# STM32.net
KiCad netlist of a schematic drawn in Altium Designer
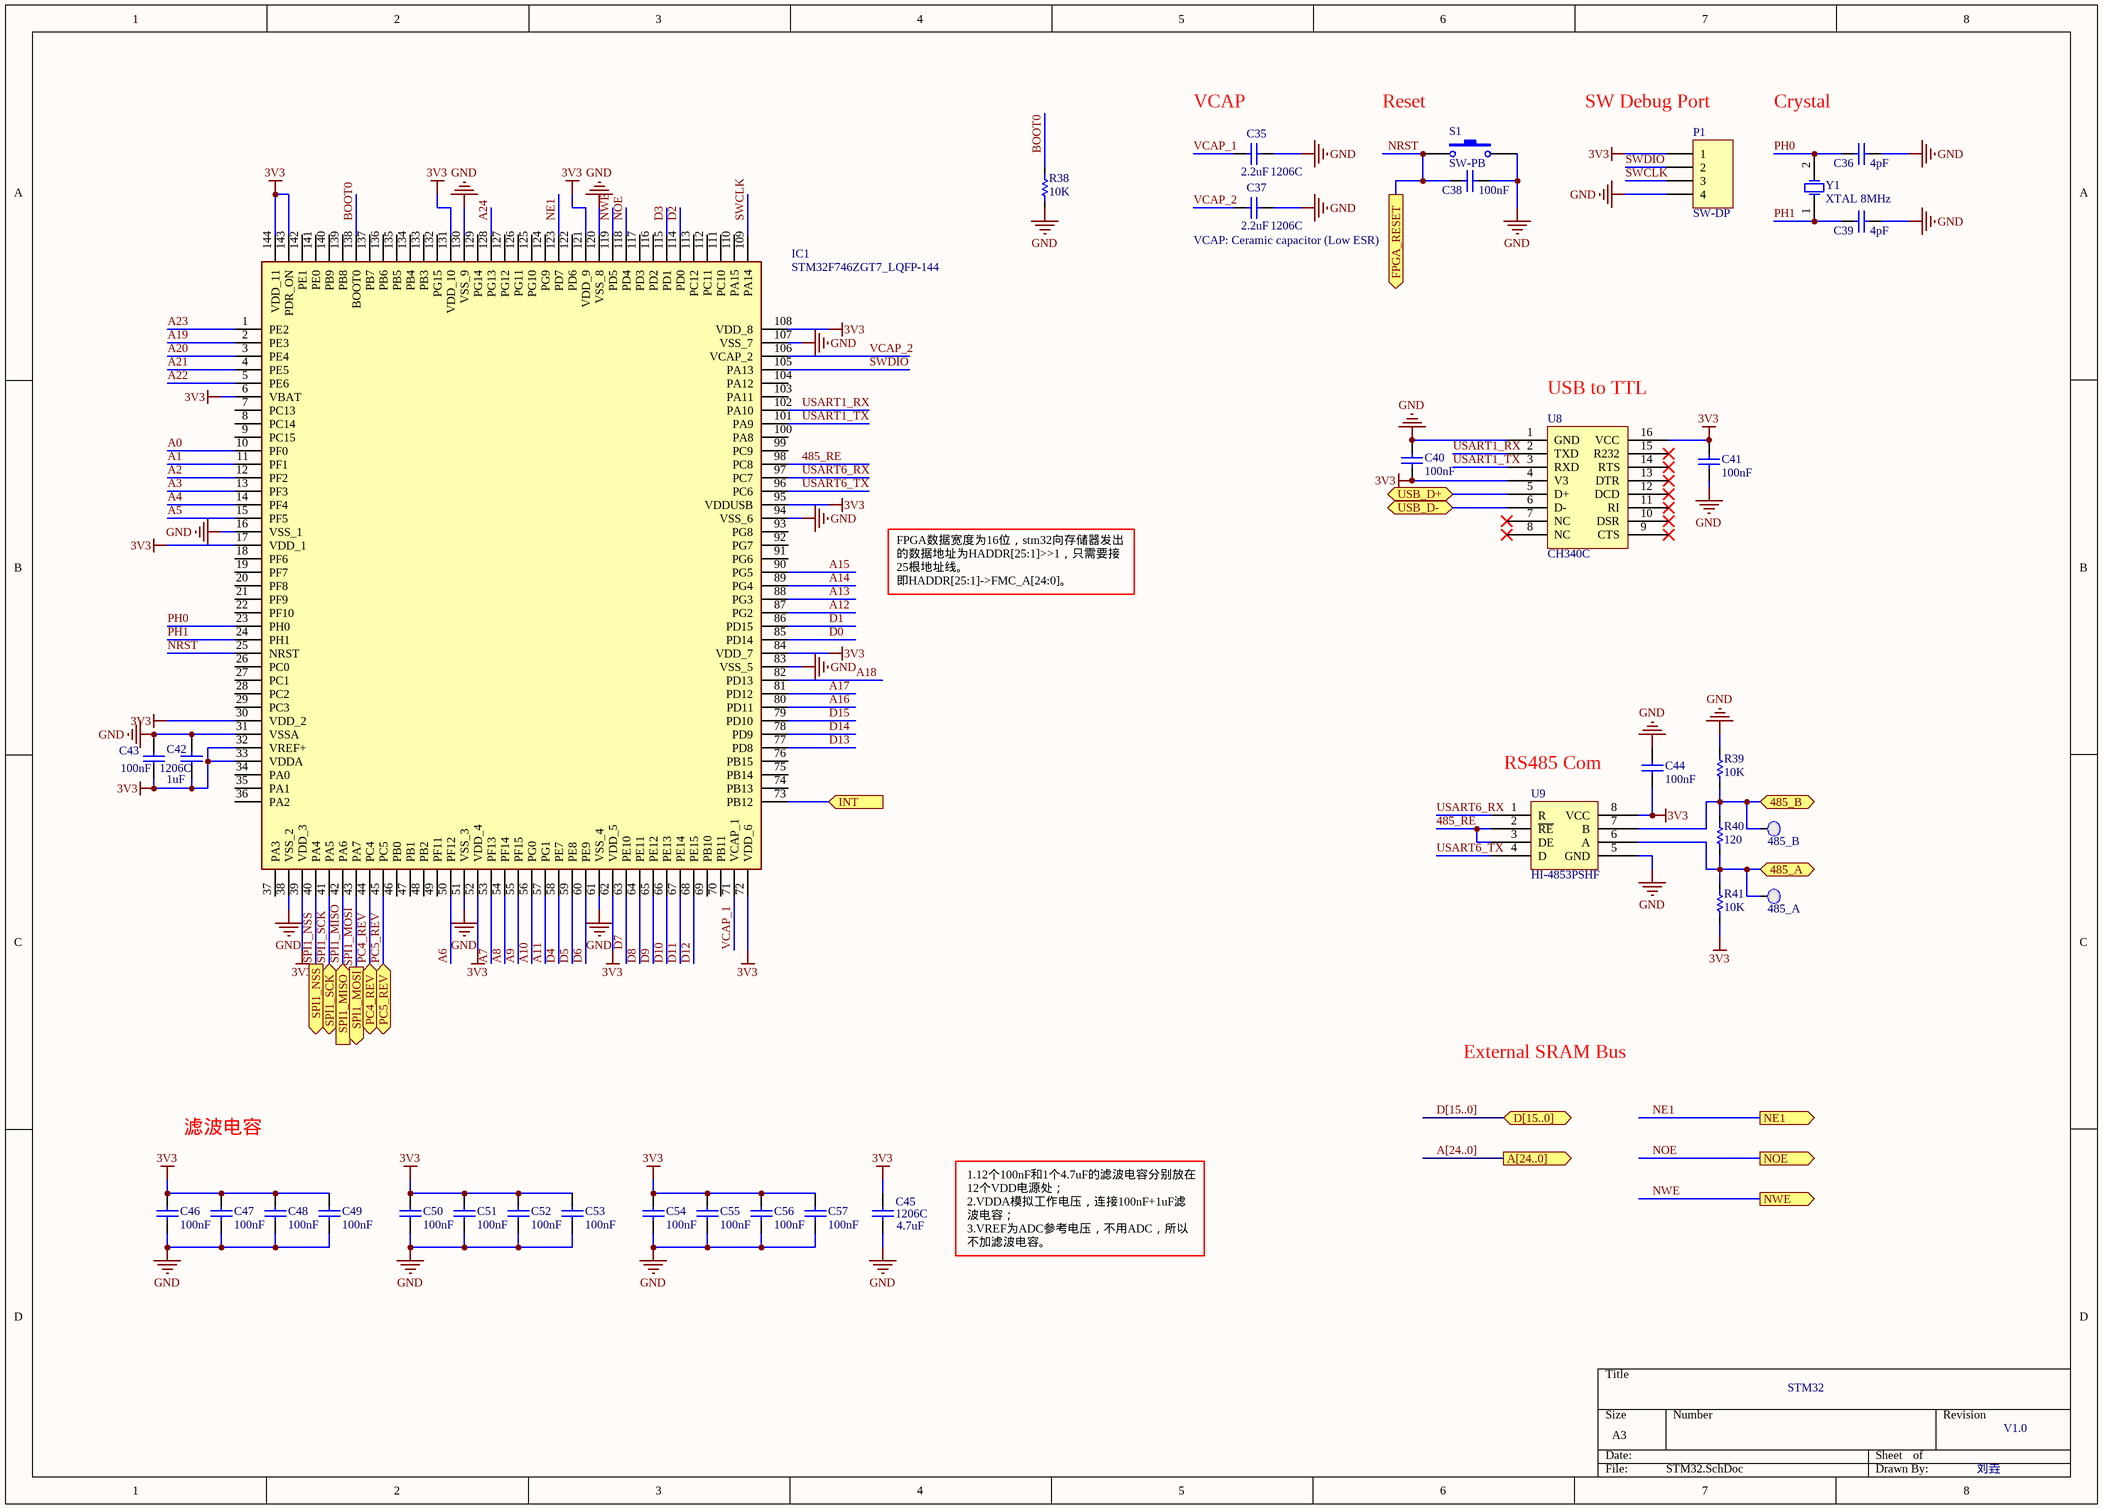
[diagram p0: STM32.SchDoc]

(export (version "E")
  (design (tool "Eeschema 10.0.6"))
  (components
    (comp (ref "485_A") (value "TP") (footprint "TPA") (libsource (lib "STM32") (part "TP")))
    (comp (ref "485_B") (value "TP") (footprint "TPA") (libsource (lib "STM32") (part "TP")))
    (comp (ref "C35")
      (value "2.2uF")
      (footprint "1206C")
      (description "Capacitor")
      (fields (field (name "PACKAGEREFERENCE") "1206C") (field (name "PUBLISHER") "Altium Limited"))
      (libsource (lib "STM32") (part "Cap"))
    )
    (comp (ref "C36")
      (value "4pF")
      (footprint "0805C")
      (description "Capacitor")
      (fields (field (name "PUBLISHER") "Altium Limited"))
      (libsource (lib "STM32") (part "Cap"))
    )
    (comp (ref "C37")
      (value "2.2uF")
      (footprint "1206C")
      (description "Capacitor")
      (fields (field (name "PACKAGEREFERENCE") "1206C") (field (name "PUBLISHER") "Altium Limited"))
      (libsource (lib "STM32") (part "Cap"))
    )
    (comp (ref "C38")
      (value "100nF")
      (footprint "0805C")
      (description "Capacitor")
      (fields (field (name "PUBLISHER") "Altium Limited"))
      (libsource (lib "STM32") (part "Cap"))
    )
    (comp (ref "C39")
      (value "4pF")
      (footprint "0805C")
      (description "Capacitor")
      (fields (field (name "PUBLISHER") "Altium Limited"))
      (libsource (lib "STM32") (part "Cap"))
    )
    (comp (ref "C40")
      (value "100nF")
      (footprint "0805C")
      (description "Capacitor")
      (fields (field (name "PUBLISHER") "Altium Limited"))
      (libsource (lib "STM32") (part "Cap"))
    )
    (comp (ref "C41")
      (value "100nF")
      (footprint "0805C")
      (description "Capacitor")
      (fields (field (name "PUBLISHER") "Altium Limited"))
      (libsource (lib "STM32") (part "Cap"))
    )
    (comp (ref "C42")
      (value "1uF")
      (footprint "1206C")
      (description "Capacitor")
      (fields (field (name "PACKAGEREFERENCE") "1206C") (field (name "PUBLISHER") "Altium Limited"))
      (libsource (lib "STM32") (part "Cap"))
    )
    (comp (ref "C43")
      (value "100nF")
      (footprint "0805C")
      (description "Capacitor")
      (fields (field (name "PUBLISHER") "Altium Limited"))
      (libsource (lib "STM32") (part "Cap"))
    )
    (comp (ref "C44")
      (value "100nF")
      (footprint "0805C")
      (description "Capacitor")
      (fields (field (name "PUBLISHER") "Altium Limited"))
      (libsource (lib "STM32") (part "Cap"))
    )
    (comp (ref "C45")
      (value "4.7uF")
      (footprint "1206C")
      (description "Capacitor")
      (fields (field (name "PACKAGEREFERENCE") "1206C") (field (name "PUBLISHER") "Altium Limited"))
      (libsource (lib "STM32") (part "Cap"))
    )
    (comp (ref "C46")
      (value "100nF")
      (footprint "0805C")
      (description "Capacitor")
      (fields (field (name "PUBLISHER") "Altium Limited"))
      (libsource (lib "STM32") (part "Cap"))
    )
    (comp (ref "C47")
      (value "100nF")
      (footprint "0805C")
      (description "Capacitor")
      (fields (field (name "PUBLISHER") "Altium Limited"))
      (libsource (lib "STM32") (part "Cap"))
    )
    (comp (ref "C48")
      (value "100nF")
      (footprint "0805C")
      (description "Capacitor")
      (fields (field (name "PUBLISHER") "Altium Limited"))
      (libsource (lib "STM32") (part "Cap"))
    )
    (comp (ref "C49")
      (value "100nF")
      (footprint "0805C")
      (description "Capacitor")
      (fields (field (name "PUBLISHER") "Altium Limited"))
      (libsource (lib "STM32") (part "Cap"))
    )
    (comp (ref "C50")
      (value "100nF")
      (footprint "0805C")
      (description "Capacitor")
      (fields (field (name "PUBLISHER") "Altium Limited"))
      (libsource (lib "STM32") (part "Cap"))
    )
    (comp (ref "C51")
      (value "100nF")
      (footprint "0805C")
      (description "Capacitor")
      (fields (field (name "PUBLISHER") "Altium Limited"))
      (libsource (lib "STM32") (part "Cap"))
    )
    (comp (ref "C52")
      (value "100nF")
      (footprint "0805C")
      (description "Capacitor")
      (fields (field (name "PUBLISHER") "Altium Limited"))
      (libsource (lib "STM32") (part "Cap"))
    )
    (comp (ref "C53")
      (value "100nF")
      (footprint "0805C")
      (description "Capacitor")
      (fields (field (name "PUBLISHER") "Altium Limited"))
      (libsource (lib "STM32") (part "Cap"))
    )
    (comp (ref "C54")
      (value "100nF")
      (footprint "0805C")
      (description "Capacitor")
      (fields (field (name "PUBLISHER") "Altium Limited"))
      (libsource (lib "STM32") (part "Cap"))
    )
    (comp (ref "C55")
      (value "100nF")
      (footprint "0805C")
      (description "Capacitor")
      (fields (field (name "PUBLISHER") "Altium Limited"))
      (libsource (lib "STM32") (part "Cap"))
    )
    (comp (ref "C56")
      (value "100nF")
      (footprint "0805C")
      (description "Capacitor")
      (fields (field (name "PUBLISHER") "Altium Limited"))
      (libsource (lib "STM32") (part "Cap"))
    )
    (comp (ref "C57")
      (value "100nF")
      (footprint "0805C")
      (description "Capacitor")
      (fields (field (name "PUBLISHER") "Altium Limited"))
      (libsource (lib "STM32") (part "Cap"))
    )
    (comp (ref "IC1")
      (value "STM32F746ZGT7_LQFP-144")
      (footprint "STM32:QFP50P2200X2200X160-144N")
      (description "Integrated Circuit")
      (fields
        (field (name "MANUFACTURER_PART_NUMBER") "STM32F746ZGT7")
        (field (name "MOUSER PART NUMBER") "511-STM32F746ZGT7")
      )
      (libsource (lib "*") (part "STM32F746ZGT7"))
    )
    (comp (ref "P1")
      (value "SW-DP")
      (footprint "MHDR1X4")
      (description "Header, 4-Pin")
      (fields (field (name "PUBLISHER") "Altium Limited"))
      (libsource (lib "Miscellaneous Connectors") (part "MHDR1X4"))
    )
    (comp (ref "R38")
      (value "10K")
      (footprint "0805R")
      (description "Resistor")
      (fields (field (name "PUBLISHER") "Altium Limited"))
      (libsource (lib "STM32") (part "Res1"))
    )
    (comp (ref "R39")
      (value "10K")
      (footprint "0805R")
      (description "Resistor")
      (fields (field (name "PUBLISHER") "Altium Limited"))
      (libsource (lib "STM32") (part "Res1"))
    )
    (comp (ref "R40")
      (value "120")
      (footprint "0805R")
      (description "Resistor")
      (fields (field (name "PUBLISHER") "Altium Limited"))
      (libsource (lib "STM32") (part "Res1"))
    )
    (comp (ref "R41")
      (value "10K")
      (footprint "0805R")
      (description "Resistor")
      (fields (field (name "PUBLISHER") "Altium Limited"))
      (libsource (lib "STM32") (part "Res1"))
    )
    (comp (ref "S1")
      (value "SW-PB")
      (footprint "SW-SMD_L6.0-W3.5-LS8.0")
      (description "Switch")
      (fields (field (name "PUBLISHER") "Altium Limited"))
      (libsource (lib "Miscellaneous Devices") (part "SW-PB"))
    )
    (comp (ref "U8") (value "CH340C") (footprint "CH340C") (libsource (lib "STM32") (part "CH340C")))
    (comp (ref "U9")
      (value "HI-4853PSHF")
      (footprint "SOIC-8N")
      (libsource (lib "STM32") (part "HI-4853PSHF"))
    )
    (comp (ref "Y1")
      (value "XTAL 8MHz")
      (footprint "NX3225GD8MHZSTDCRA3")
      (description "Crystal Oscillator")
      (fields (field (name "PUBLISHER") "Altium Limited"))
      (libsource (lib "STM32") (part "XTAL"))
    )
  )
  (nets
    (net (code "1") (name "/485_A") (class "Default")
      (node (ref "485_A") (pin "1") (pinfunction "TP_1") (pintype "passive"))
      (node (ref "R40") (pin "1") (pinfunction "1_1") (pintype "passive"))
      (node (ref "R41") (pin "2") (pinfunction "2_2") (pintype "passive"))
      (node (ref "U9") (pin "6") (pinfunction "A_6") (pintype "passive"))
    )
    (net (code "2") (name "/485_B") (class "Default")
      (node (ref "485_B") (pin "1") (pinfunction "TP_1") (pintype "passive"))
      (node (ref "R39") (pin "1") (pinfunction "1_1") (pintype "passive"))
      (node (ref "R40") (pin "2") (pinfunction "2_2") (pintype "passive"))
      (node (ref "U9") (pin "7") (pinfunction "B_7") (pintype "passive"))
    )
    (net (code "3") (name "/485_RE") (class "Default")
      (node (ref "IC1") (pin "98") (pinfunction "PC8_98") (pintype "passive"))
      (node (ref "U9") (pin "2") (pinfunction "~{RE}_2") (pintype "passive"))
      (node (ref "U9") (pin "3") (pinfunction "DE_3") (pintype "passive"))
    )
    (net (code "4") (name "/A0") (class "Default")
      (node (ref "IC1") (pin "10") (pinfunction "PF0_10") (pintype "passive"))
    )
    (net (code "5") (name "/A1") (class "Default")
      (node (ref "IC1") (pin "11") (pinfunction "PF1_11") (pintype "passive"))
    )
    (net (code "6") (name "/A2") (class "Default")
      (node (ref "IC1") (pin "12") (pinfunction "PF2_12") (pintype "passive"))
    )
    (net (code "7") (name "/A3") (class "Default")
      (node (ref "IC1") (pin "13") (pinfunction "PF3_13") (pintype "passive"))
    )
    (net (code "8") (name "/A4") (class "Default")
      (node (ref "IC1") (pin "14") (pinfunction "PF4_14") (pintype "passive"))
    )
    (net (code "9") (name "/A5") (class "Default")
      (node (ref "IC1") (pin "15") (pinfunction "PF5_15") (pintype "passive"))
    )
    (net (code "10") (name "/A6") (class "Default")
      (node (ref "IC1") (pin "50") (pinfunction "PF12_50") (pintype "passive"))
    )
    (net (code "11") (name "/A7") (class "Default")
      (node (ref "IC1") (pin "53") (pinfunction "PF13_53") (pintype "passive"))
    )
    (net (code "12") (name "/A8") (class "Default")
      (node (ref "IC1") (pin "54") (pinfunction "PF14_54") (pintype "passive"))
    )
    (net (code "13") (name "/A9") (class "Default")
      (node (ref "IC1") (pin "55") (pinfunction "PF15_55") (pintype "passive"))
    )
    (net (code "14") (name "/A10") (class "Default")
      (node (ref "IC1") (pin "56") (pinfunction "PG0_56") (pintype "passive"))
    )
    (net (code "15") (name "/A11") (class "Default")
      (node (ref "IC1") (pin "57") (pinfunction "PG1_57") (pintype "passive"))
    )
    (net (code "16") (name "/A12") (class "Default")
      (node (ref "IC1") (pin "87") (pinfunction "PG2_87") (pintype "passive"))
    )
    (net (code "17") (name "/A13") (class "Default")
      (node (ref "IC1") (pin "88") (pinfunction "PG3_88") (pintype "passive"))
    )
    (net (code "18") (name "/A14") (class "Default")
      (node (ref "IC1") (pin "89") (pinfunction "PG4_89") (pintype "passive"))
    )
    (net (code "19") (name "/A15") (class "Default")
      (node (ref "IC1") (pin "90") (pinfunction "PG5_90") (pintype "passive"))
    )
    (net (code "20") (name "/A16") (class "Default")
      (node (ref "IC1") (pin "80") (pinfunction "PD11_80") (pintype "passive"))
    )
    (net (code "21") (name "/A17") (class "Default")
      (node (ref "IC1") (pin "81") (pinfunction "PD12_81") (pintype "passive"))
    )
    (net (code "22") (name "/A18") (class "Default")
      (node (ref "IC1") (pin "82") (pinfunction "PD13_82") (pintype "passive"))
    )
    (net (code "23") (name "/A19") (class "Default")
      (node (ref "IC1") (pin "2") (pinfunction "PE3_2") (pintype "passive"))
    )
    (net (code "24") (name "/A20") (class "Default")
      (node (ref "IC1") (pin "3") (pinfunction "PE4_3") (pintype "passive"))
    )
    (net (code "25") (name "/A21") (class "Default")
      (node (ref "IC1") (pin "4") (pinfunction "PE5_4") (pintype "passive"))
    )
    (net (code "26") (name "/A22") (class "Default")
      (node (ref "IC1") (pin "5") (pinfunction "PE6_5") (pintype "passive"))
    )
    (net (code "27") (name "/A23") (class "Default")
      (node (ref "IC1") (pin "1") (pinfunction "PE2_1") (pintype "passive"))
    )
    (net (code "28") (name "/A24") (class "Default")
      (node (ref "IC1") (pin "128") (pinfunction "PG13_128") (pintype "passive"))
    )
    (net (code "30") (name "/BOOT0") (class "Default")
      (node (ref "IC1") (pin "138") (pinfunction "BOOT0_138") (pintype "passive"))
      (node (ref "R38") (pin "1") (pinfunction "1_1") (pintype "passive"))
    )
    (net (code "31") (name "/D0") (class "Default")
      (node (ref "IC1") (pin "85") (pinfunction "PD14_85") (pintype "passive"))
    )
    (net (code "32") (name "/D1") (class "Default")
      (node (ref "IC1") (pin "86") (pinfunction "PD15_86") (pintype "passive"))
    )
    (net (code "33") (name "/D2") (class "Default")
      (node (ref "IC1") (pin "114") (pinfunction "PD0_114") (pintype "passive"))
    )
    (net (code "34") (name "/D3") (class "Default")
      (node (ref "IC1") (pin "115") (pinfunction "PD1_115") (pintype "passive"))
    )
    (net (code "35") (name "/D4") (class "Default")
      (node (ref "IC1") (pin "58") (pinfunction "PE7_58") (pintype "passive"))
    )
    (net (code "36") (name "/D5") (class "Default")
      (node (ref "IC1") (pin "59") (pinfunction "PE8_59") (pintype "passive"))
    )
    (net (code "37") (name "/D6") (class "Default")
      (node (ref "IC1") (pin "60") (pinfunction "PE9_60") (pintype "passive"))
    )
    (net (code "38") (name "/D7") (class "Default")
      (node (ref "IC1") (pin "63") (pinfunction "PE10_63") (pintype "passive"))
    )
    (net (code "39") (name "/D8") (class "Default")
      (node (ref "IC1") (pin "64") (pinfunction "PE11_64") (pintype "passive"))
    )
    (net (code "40") (name "/D9") (class "Default")
      (node (ref "IC1") (pin "65") (pinfunction "PE12_65") (pintype "passive"))
    )
    (net (code "41") (name "/D10") (class "Default")
      (node (ref "IC1") (pin "66") (pinfunction "PE13_66") (pintype "passive"))
    )
    (net (code "42") (name "/D11") (class "Default")
      (node (ref "IC1") (pin "67") (pinfunction "PE14_67") (pintype "passive"))
    )
    (net (code "43") (name "/D12") (class "Default")
      (node (ref "IC1") (pin "68") (pinfunction "PE15_68") (pintype "passive"))
    )
    (net (code "44") (name "/D13") (class "Default")
      (node (ref "IC1") (pin "77") (pinfunction "PD8_77") (pintype "passive"))
    )
    (net (code "45") (name "/D14") (class "Default")
      (node (ref "IC1") (pin "78") (pinfunction "PD9_78") (pintype "passive"))
    )
    (net (code "46") (name "/D15") (class "Default")
      (node (ref "IC1") (pin "79") (pinfunction "PD10_79") (pintype "passive"))
    )
    (net (code "48") (name "/INT") (class "Default")
      (node (ref "IC1") (pin "73") (pinfunction "PB12_73") (pintype "passive"))
    )
    (net (code "49") (name "/NE1") (class "Default")
      (node (ref "IC1") (pin "123") (pinfunction "PD7_123") (pintype "passive"))
    )
    (net (code "50") (name "/NOE") (class "Default")
      (node (ref "IC1") (pin "118") (pinfunction "PD4_118") (pintype "passive"))
    )
    (net (code "51") (name "/NRST") (class "Default")
      (node (ref "C38") (pin "1") (pinfunction "1_1") (pintype "passive"))
      (node (ref "IC1") (pin "25") (pinfunction "NRST_25") (pintype "passive"))
      (node (ref "S1") (pin "1") (pinfunction "1_1") (pintype "passive"))
    )
    (net (code "52") (name "/NWE") (class "Default")
      (node (ref "IC1") (pin "119") (pinfunction "PD5_119") (pintype "passive"))
    )
    (net (code "53") (name "/PC4_REV") (class "Default")
      (node (ref "IC1") (pin "44") (pinfunction "PC4_44") (pintype "passive"))
    )
    (net (code "54") (name "/PC5_REV") (class "Default")
      (node (ref "IC1") (pin "45") (pinfunction "PC5_45") (pintype "passive"))
    )
    (net (code "55") (name "/PH0") (class "Default")
      (node (ref "C36") (pin "1") (pinfunction "1_1") (pintype "passive"))
      (node (ref "IC1") (pin "23") (pinfunction "PH0_23") (pintype "passive"))
      (node (ref "Y1") (pin "2") (pinfunction "OSC2_2") (pintype "passive"))
    )
    (net (code "56") (name "/PH1") (class "Default")
      (node (ref "C39") (pin "1") (pinfunction "1_1") (pintype "passive"))
      (node (ref "IC1") (pin "24") (pinfunction "PH1_24") (pintype "passive"))
      (node (ref "Y1") (pin "1") (pinfunction "OSC1_1") (pintype "passive"))
    )
    (net (code "57") (name "/SPI1_MISO") (class "Default")
      (node (ref "IC1") (pin "42") (pinfunction "PA6_42") (pintype "passive"))
    )
    (net (code "58") (name "/SPI1_MOSI") (class "Default")
      (node (ref "IC1") (pin "43") (pinfunction "PA7_43") (pintype "passive"))
    )
    (net (code "59") (name "/SPI1_NSS") (class "Default")
      (node (ref "IC1") (pin "40") (pinfunction "PA4_40") (pintype "passive"))
    )
    (net (code "60") (name "/SPI1_SCK") (class "Default")
      (node (ref "IC1") (pin "41") (pinfunction "PA5_41") (pintype "passive"))
    )
    (net (code "61") (name "/SWCLK") (class "Default")
      (node (ref "IC1") (pin "109") (pinfunction "PA14_109") (pintype "passive"))
      (node (ref "P1") (pin "3") (pinfunction "3_3") (pintype "passive"))
    )
    (net (code "62") (name "/SWDIO") (class "Default")
      (node (ref "IC1") (pin "105") (pinfunction "PA13_105") (pintype "passive"))
      (node (ref "P1") (pin "2") (pinfunction "2_2") (pintype "passive"))
    )
    (net (code "63") (name "/USART1_RX") (class "Default")
      (node (ref "IC1") (pin "102") (pinfunction "PA10_102") (pintype "passive"))
      (node (ref "U8") (pin "2") (pinfunction "TXD_2") (pintype "passive"))
    )
    (net (code "64") (name "/USART1_TX") (class "Default")
      (node (ref "IC1") (pin "101") (pinfunction "PA9_101") (pintype "passive"))
      (node (ref "U8") (pin "3") (pinfunction "RXD_3") (pintype "passive"))
    )
    (net (code "65") (name "/USART6_RX") (class "Default")
      (node (ref "IC1") (pin "97") (pinfunction "PC7_97") (pintype "passive"))
      (node (ref "U9") (pin "1") (pinfunction "R_1") (pintype "passive"))
    )
    (net (code "66") (name "/USART6_TX") (class "Default")
      (node (ref "IC1") (pin "96") (pinfunction "PC6_96") (pintype "passive"))
      (node (ref "U9") (pin "4") (pinfunction "D_4") (pintype "passive"))
    )
    (net (code "67") (name "/USB_D+") (class "Default")
      (node (ref "U8") (pin "5") (pinfunction "D+_5") (pintype "passive"))
    )
    (net (code "68") (name "/USB_D-") (class "Default")
      (node (ref "U8") (pin "6") (pinfunction "D-_6") (pintype "passive"))
    )
    (net (code "69") (name "/VCAP_1") (class "Default")
      (node (ref "C35") (pin "2") (pinfunction "2_2") (pintype "passive"))
      (node (ref "IC1") (pin "71") (pinfunction "VCAP_1_71") (pintype "passive"))
    )
    (net (code "70") (name "/VCAP_2") (class "Default")
      (node (ref "C37") (pin "2") (pinfunction "2_2") (pintype "passive"))
      (node (ref "IC1") (pin "106") (pinfunction "VCAP_2_106") (pintype "passive"))
    )
    (net (code "71") (name "3V3") (class "Default")
      (node (ref "C40") (pin "1") (pinfunction "1_1") (pintype "passive"))
      (node (ref "C41") (pin "2") (pinfunction "2_2") (pintype "passive"))
      (node (ref "C42") (pin "1") (pinfunction "1_1") (pintype "passive"))
      (node (ref "C43") (pin "1") (pinfunction "1_1") (pintype "passive"))
      (node (ref "C44") (pin "1") (pinfunction "1_1") (pintype "passive"))
      (node (ref "C45") (pin "2") (pinfunction "2_2") (pintype "passive"))
      (node (ref "C46") (pin "2") (pinfunction "2_2") (pintype "passive"))
      (node (ref "C47") (pin "2") (pinfunction "2_2") (pintype "passive"))
      (node (ref "C48") (pin "2") (pinfunction "2_2") (pintype "passive"))
      (node (ref "C49") (pin "2") (pinfunction "2_2") (pintype "passive"))
      (node (ref "C50") (pin "2") (pinfunction "2_2") (pintype "passive"))
      (node (ref "C51") (pin "2") (pinfunction "2_2") (pintype "passive"))
      (node (ref "C52") (pin "2") (pinfunction "2_2") (pintype "passive"))
      (node (ref "C53") (pin "2") (pinfunction "2_2") (pintype "passive"))
      (node (ref "C54") (pin "2") (pinfunction "2_2") (pintype "passive"))
      (node (ref "C55") (pin "2") (pinfunction "2_2") (pintype "passive"))
      (node (ref "C56") (pin "2") (pinfunction "2_2") (pintype "passive"))
      (node (ref "C57") (pin "2") (pinfunction "2_2") (pintype "passive"))
      (node (ref "IC1") (pin "108") (pinfunction "VDD_8_108") (pintype "passive"))
      (node (ref "IC1") (pin "121") (pinfunction "VDD_9_121") (pintype "passive"))
      (node (ref "IC1") (pin "131") (pinfunction "VDD_10_131") (pintype "passive"))
      (node (ref "IC1") (pin "143") (pinfunction "PDR_ON_143") (pintype "passive"))
      (node (ref "IC1") (pin "144") (pinfunction "VDD_11_144") (pintype "passive"))
      (node (ref "IC1") (pin "17") (pinfunction "VDD_1_17") (pintype "passive"))
      (node (ref "IC1") (pin "30") (pinfunction "VDD_2_30") (pintype "passive"))
      (node (ref "IC1") (pin "32") (pinfunction "VREF+_32") (pintype "passive"))
      (node (ref "IC1") (pin "33") (pinfunction "VDDA_33") (pintype "passive"))
      (node (ref "IC1") (pin "39") (pinfunction "VDD_3_39") (pintype "passive"))
      (node (ref "IC1") (pin "52") (pinfunction "VDD_4_52") (pintype "passive"))
      (node (ref "IC1") (pin "6") (pinfunction "VBAT_6") (pintype "passive"))
      (node (ref "IC1") (pin "62") (pinfunction "VDD_5_62") (pintype "passive"))
      (node (ref "IC1") (pin "72") (pinfunction "VDD_6_72") (pintype "passive"))
      (node (ref "IC1") (pin "84") (pinfunction "VDD_7_84") (pintype "passive"))
      (node (ref "IC1") (pin "95") (pinfunction "VDDUSB_95") (pintype "passive"))
      (node (ref "P1") (pin "1") (pinfunction "1_1") (pintype "passive"))
      (node (ref "R41") (pin "1") (pinfunction "1_1") (pintype "passive"))
      (node (ref "U8") (pin "16") (pinfunction "VCC_16") (pintype "passive"))
      (node (ref "U8") (pin "4") (pinfunction "V3_4") (pintype "power_in"))
      (node (ref "U9") (pin "8") (pinfunction "VCC_8") (pintype "passive"))
    )
    (net (code "72") (name "GND") (class "Default")
      (node (ref "C35") (pin "1") (pinfunction "1_1") (pintype "passive"))
      (node (ref "C36") (pin "2") (pinfunction "2_2") (pintype "passive"))
      (node (ref "C37") (pin "1") (pinfunction "1_1") (pintype "passive"))
      (node (ref "C38") (pin "2") (pinfunction "2_2") (pintype "passive"))
      (node (ref "C39") (pin "2") (pinfunction "2_2") (pintype "passive"))
      (node (ref "C40") (pin "2") (pinfunction "2_2") (pintype "passive"))
      (node (ref "C41") (pin "1") (pinfunction "1_1") (pintype "passive"))
      (node (ref "C42") (pin "2") (pinfunction "2_2") (pintype "passive"))
      (node (ref "C43") (pin "2") (pinfunction "2_2") (pintype "passive"))
      (node (ref "C44") (pin "2") (pinfunction "2_2") (pintype "passive"))
      (node (ref "C45") (pin "1") (pinfunction "1_1") (pintype "passive"))
      (node (ref "C46") (pin "1") (pinfunction "1_1") (pintype "passive"))
      (node (ref "C47") (pin "1") (pinfunction "1_1") (pintype "passive"))
      (node (ref "C48") (pin "1") (pinfunction "1_1") (pintype "passive"))
      (node (ref "C49") (pin "1") (pinfunction "1_1") (pintype "passive"))
      (node (ref "C50") (pin "1") (pinfunction "1_1") (pintype "passive"))
      (node (ref "C51") (pin "1") (pinfunction "1_1") (pintype "passive"))
      (node (ref "C52") (pin "1") (pinfunction "1_1") (pintype "passive"))
      (node (ref "C53") (pin "1") (pinfunction "1_1") (pintype "passive"))
      (node (ref "C54") (pin "1") (pinfunction "1_1") (pintype "passive"))
      (node (ref "C55") (pin "1") (pinfunction "1_1") (pintype "passive"))
      (node (ref "C56") (pin "1") (pinfunction "1_1") (pintype "passive"))
      (node (ref "C57") (pin "1") (pinfunction "1_1") (pintype "passive"))
      (node (ref "IC1") (pin "107") (pinfunction "VSS_7_107") (pintype "passive"))
      (node (ref "IC1") (pin "120") (pinfunction "VSS_8_120") (pintype "passive"))
      (node (ref "IC1") (pin "130") (pinfunction "VSS_9_130") (pintype "passive"))
      (node (ref "IC1") (pin "16") (pinfunction "VSS_1_16") (pintype "passive"))
      (node (ref "IC1") (pin "31") (pinfunction "VSSA_31") (pintype "passive"))
      (node (ref "IC1") (pin "38") (pinfunction "VSS_2_38") (pintype "passive"))
      (node (ref "IC1") (pin "51") (pinfunction "VSS_3_51") (pintype "passive"))
      (node (ref "IC1") (pin "61") (pinfunction "VSS_4_61") (pintype "passive"))
      (node (ref "IC1") (pin "83") (pinfunction "VSS_5_83") (pintype "passive"))
      (node (ref "IC1") (pin "94") (pinfunction "VSS_6_94") (pintype "passive"))
      (node (ref "P1") (pin "4") (pinfunction "4_4") (pintype "passive"))
      (node (ref "R38") (pin "2") (pinfunction "2_2") (pintype "passive"))
      (node (ref "R39") (pin "2") (pinfunction "2_2") (pintype "passive"))
      (node (ref "S1") (pin "2") (pinfunction "2_2") (pintype "passive"))
      (node (ref "U8") (pin "1") (pinfunction "GND_1") (pintype "passive"))
      (node (ref "U9") (pin "5") (pinfunction "GND_5") (pintype "passive"))
    )
    (net (code "73") (name "unconnected-(IC1-PA0-Pad34)") (class "Default")
      (node (ref "IC1") (pin "34") (pinfunction "PA0_34") (pintype "passive"))
    )
    (net (code "74") (name "unconnected-(IC1-PA1-Pad35)") (class "Default")
      (node (ref "IC1") (pin "35") (pinfunction "PA1_35") (pintype "passive"))
    )
    (net (code "75") (name "unconnected-(IC1-PA2-Pad36)") (class "Default")
      (node (ref "IC1") (pin "36") (pinfunction "PA2_36") (pintype "passive"))
    )
    (net (code "76") (name "unconnected-(IC1-PA3-Pad37)") (class "Default")
      (node (ref "IC1") (pin "37") (pinfunction "PA3_37") (pintype "passive"))
    )
    (net (code "77") (name "unconnected-(IC1-PA8-Pad100)") (class "Default")
      (node (ref "IC1") (pin "100") (pinfunction "PA8_100") (pintype "passive"))
    )
    (net (code "78") (name "unconnected-(IC1-PA11-Pad103)") (class "Default")
      (node (ref "IC1") (pin "103") (pinfunction "PA11_103") (pintype "passive"))
    )
    (net (code "79") (name "unconnected-(IC1-PA12-Pad104)") (class "Default")
      (node (ref "IC1") (pin "104") (pinfunction "PA12_104") (pintype "passive"))
    )
    (net (code "80") (name "unconnected-(IC1-PA15-Pad110)") (class "Default")
      (node (ref "IC1") (pin "110") (pinfunction "PA15_110") (pintype "passive"))
    )
    (net (code "81") (name "unconnected-(IC1-PB0-Pad46)") (class "Default")
      (node (ref "IC1") (pin "46") (pinfunction "PB0_46") (pintype "passive"))
    )
    (net (code "82") (name "unconnected-(IC1-PB1-Pad47)") (class "Default")
      (node (ref "IC1") (pin "47") (pinfunction "PB1_47") (pintype "passive"))
    )
    (net (code "83") (name "unconnected-(IC1-PB2-Pad48)") (class "Default")
      (node (ref "IC1") (pin "48") (pinfunction "PB2_48") (pintype "passive"))
    )
    (net (code "84") (name "unconnected-(IC1-PB3-Pad133)") (class "Default")
      (node (ref "IC1") (pin "133") (pinfunction "PB3_133") (pintype "passive"))
    )
    (net (code "85") (name "unconnected-(IC1-PB4-Pad134)") (class "Default")
      (node (ref "IC1") (pin "134") (pinfunction "PB4_134") (pintype "passive"))
    )
    (net (code "86") (name "unconnected-(IC1-PB5-Pad135)") (class "Default")
      (node (ref "IC1") (pin "135") (pinfunction "PB5_135") (pintype "passive"))
    )
    (net (code "87") (name "unconnected-(IC1-PB6-Pad136)") (class "Default")
      (node (ref "IC1") (pin "136") (pinfunction "PB6_136") (pintype "passive"))
    )
    (net (code "88") (name "unconnected-(IC1-PB7-Pad137)") (class "Default")
      (node (ref "IC1") (pin "137") (pinfunction "PB7_137") (pintype "passive"))
    )
    (net (code "89") (name "unconnected-(IC1-PB8-Pad139)") (class "Default")
      (node (ref "IC1") (pin "139") (pinfunction "PB8_139") (pintype "passive"))
    )
    (net (code "90") (name "unconnected-(IC1-PB9-Pad140)") (class "Default")
      (node (ref "IC1") (pin "140") (pinfunction "PB9_140") (pintype "passive"))
    )
    (net (code "91") (name "unconnected-(IC1-PB10-Pad69)") (class "Default")
      (node (ref "IC1") (pin "69") (pinfunction "PB10_69") (pintype "passive"))
    )
    (net (code "92") (name "unconnected-(IC1-PB11-Pad70)") (class "Default")
      (node (ref "IC1") (pin "70") (pinfunction "PB11_70") (pintype "passive"))
    )
    (net (code "93") (name "unconnected-(IC1-PB13-Pad74)") (class "Default")
      (node (ref "IC1") (pin "74") (pinfunction "PB13_74") (pintype "passive"))
    )
    (net (code "94") (name "unconnected-(IC1-PB14-Pad75)") (class "Default")
      (node (ref "IC1") (pin "75") (pinfunction "PB14_75") (pintype "passive"))
    )
    (net (code "95") (name "unconnected-(IC1-PB15-Pad76)") (class "Default")
      (node (ref "IC1") (pin "76") (pinfunction "PB15_76") (pintype "passive"))
    )
    (net (code "96") (name "unconnected-(IC1-PC0-Pad26)") (class "Default")
      (node (ref "IC1") (pin "26") (pinfunction "PC0_26") (pintype "passive"))
    )
    (net (code "97") (name "unconnected-(IC1-PC1-Pad27)") (class "Default")
      (node (ref "IC1") (pin "27") (pinfunction "PC1_27") (pintype "passive"))
    )
    (net (code "98") (name "unconnected-(IC1-PC2-Pad28)") (class "Default")
      (node (ref "IC1") (pin "28") (pinfunction "PC2_28") (pintype "passive"))
    )
    (net (code "99") (name "unconnected-(IC1-PC3-Pad29)") (class "Default")
      (node (ref "IC1") (pin "29") (pinfunction "PC3_29") (pintype "passive"))
    )
    (net (code "100") (name "unconnected-(IC1-PC9-Pad99)") (class "Default")
      (node (ref "IC1") (pin "99") (pinfunction "PC9_99") (pintype "passive"))
    )
    (net (code "101") (name "unconnected-(IC1-PC10-Pad111)") (class "Default")
      (node (ref "IC1") (pin "111") (pinfunction "PC10_111") (pintype "passive"))
    )
    (net (code "102") (name "unconnected-(IC1-PC11-Pad112)") (class "Default")
      (node (ref "IC1") (pin "112") (pinfunction "PC11_112") (pintype "passive"))
    )
    (net (code "103") (name "unconnected-(IC1-PC12-Pad113)") (class "Default")
      (node (ref "IC1") (pin "113") (pinfunction "PC12_113") (pintype "passive"))
    )
    (net (code "104") (name "unconnected-(IC1-PC13-Pad7)") (class "Default")
      (node (ref "IC1") (pin "7") (pinfunction "PC13_7") (pintype "passive"))
    )
    (net (code "105") (name "unconnected-(IC1-PC14-Pad8)") (class "Default")
      (node (ref "IC1") (pin "8") (pinfunction "PC14_8") (pintype "passive"))
    )
    (net (code "106") (name "unconnected-(IC1-PC15-Pad9)") (class "Default")
      (node (ref "IC1") (pin "9") (pinfunction "PC15_9") (pintype "passive"))
    )
    (net (code "107") (name "unconnected-(IC1-PD2-Pad116)") (class "Default")
      (node (ref "IC1") (pin "116") (pinfunction "PD2_116") (pintype "passive"))
    )
    (net (code "108") (name "unconnected-(IC1-PD3-Pad117)") (class "Default")
      (node (ref "IC1") (pin "117") (pinfunction "PD3_117") (pintype "passive"))
    )
    (net (code "109") (name "unconnected-(IC1-PD6-Pad122)") (class "Default")
      (node (ref "IC1") (pin "122") (pinfunction "PD6_122") (pintype "passive"))
    )
    (net (code "110") (name "unconnected-(IC1-PE0-Pad141)") (class "Default")
      (node (ref "IC1") (pin "141") (pinfunction "PE0_141") (pintype "passive"))
    )
    (net (code "111") (name "unconnected-(IC1-PE1-Pad142)") (class "Default")
      (node (ref "IC1") (pin "142") (pinfunction "PE1_142") (pintype "passive"))
    )
    (net (code "112") (name "unconnected-(IC1-PF6-Pad18)") (class "Default")
      (node (ref "IC1") (pin "18") (pinfunction "PF6_18") (pintype "passive"))
    )
    (net (code "113") (name "unconnected-(IC1-PF7-Pad19)") (class "Default")
      (node (ref "IC1") (pin "19") (pinfunction "PF7_19") (pintype "passive"))
    )
    (net (code "114") (name "unconnected-(IC1-PF8-Pad20)") (class "Default")
      (node (ref "IC1") (pin "20") (pinfunction "PF8_20") (pintype "passive"))
    )
    (net (code "115") (name "unconnected-(IC1-PF9-Pad21)") (class "Default")
      (node (ref "IC1") (pin "21") (pinfunction "PF9_21") (pintype "passive"))
    )
    (net (code "116") (name "unconnected-(IC1-PF10-Pad22)") (class "Default")
      (node (ref "IC1") (pin "22") (pinfunction "PF10_22") (pintype "passive"))
    )
    (net (code "117") (name "unconnected-(IC1-PF11-Pad49)") (class "Default")
      (node (ref "IC1") (pin "49") (pinfunction "PF11_49") (pintype "passive"))
    )
    (net (code "118") (name "unconnected-(IC1-PG6-Pad91)") (class "Default")
      (node (ref "IC1") (pin "91") (pinfunction "PG6_91") (pintype "passive"))
    )
    (net (code "119") (name "unconnected-(IC1-PG7-Pad92)") (class "Default")
      (node (ref "IC1") (pin "92") (pinfunction "PG7_92") (pintype "passive"))
    )
    (net (code "120") (name "unconnected-(IC1-PG8-Pad93)") (class "Default")
      (node (ref "IC1") (pin "93") (pinfunction "PG8_93") (pintype "passive"))
    )
    (net (code "121") (name "unconnected-(IC1-PG9-Pad124)") (class "Default")
      (node (ref "IC1") (pin "124") (pinfunction "PG9_124") (pintype "passive"))
    )
    (net (code "122") (name "unconnected-(IC1-PG10-Pad125)") (class "Default")
      (node (ref "IC1") (pin "125") (pinfunction "PG10_125") (pintype "passive"))
    )
    (net (code "123") (name "unconnected-(IC1-PG11-Pad126)") (class "Default")
      (node (ref "IC1") (pin "126") (pinfunction "PG11_126") (pintype "passive"))
    )
    (net (code "124") (name "unconnected-(IC1-PG12-Pad127)") (class "Default")
      (node (ref "IC1") (pin "127") (pinfunction "PG12_127") (pintype "passive"))
    )
    (net (code "125") (name "unconnected-(IC1-PG14-Pad129)") (class "Default")
      (node (ref "IC1") (pin "129") (pinfunction "PG14_129") (pintype "passive"))
    )
    (net (code "126") (name "unconnected-(IC1-PG15-Pad132)") (class "Default")
      (node (ref "IC1") (pin "132") (pinfunction "PG15_132") (pintype "passive"))
    )
    (net (code "127") (name "unconnected-(U8-CTS-Pad9)") (class "Default")
      (node (ref "U8") (pin "9") (pinfunction "CTS_9") (pintype "passive+no_connect"))
    )
    (net (code "128") (name "unconnected-(U8-DCD-Pad12)") (class "Default")
      (node (ref "U8") (pin "12") (pinfunction "DCD_12") (pintype "passive+no_connect"))
    )
    (net (code "129") (name "unconnected-(U8-DSR-Pad10)") (class "Default")
      (node (ref "U8") (pin "10") (pinfunction "DSR_10") (pintype "passive+no_connect"))
    )
    (net (code "130") (name "unconnected-(U8-DTR-Pad13)") (class "Default")
      (node (ref "U8") (pin "13") (pinfunction "DTR_13") (pintype "passive+no_connect"))
    )
    (net (code "131") (name "unconnected-(U8-NC-Pad7)") (class "Default")
      (node (ref "U8") (pin "7") (pinfunction "NC_7") (pintype "passive+no_connect"))
    )
    (net (code "132") (name "unconnected-(U8-NC-Pad8)") (class "Default")
      (node (ref "U8") (pin "8") (pinfunction "NC_8") (pintype "passive+no_connect"))
    )
    (net (code "133") (name "unconnected-(U8-R232-Pad15)") (class "Default")
      (node (ref "U8") (pin "15") (pinfunction "R232_15") (pintype "passive+no_connect"))
    )
    (net (code "134") (name "unconnected-(U8-RI-Pad11)") (class "Default")
      (node (ref "U8") (pin "11") (pinfunction "RI_11") (pintype "passive+no_connect"))
    )
    (net (code "135") (name "unconnected-(U8-RTS-Pad14)") (class "Default")
      (node (ref "U8") (pin "14") (pinfunction "RTS_14") (pintype "passive+no_connect"))
    )
  )
)
